# sensor.net
KiCad netlist of a schematic drawn in Altium Designer
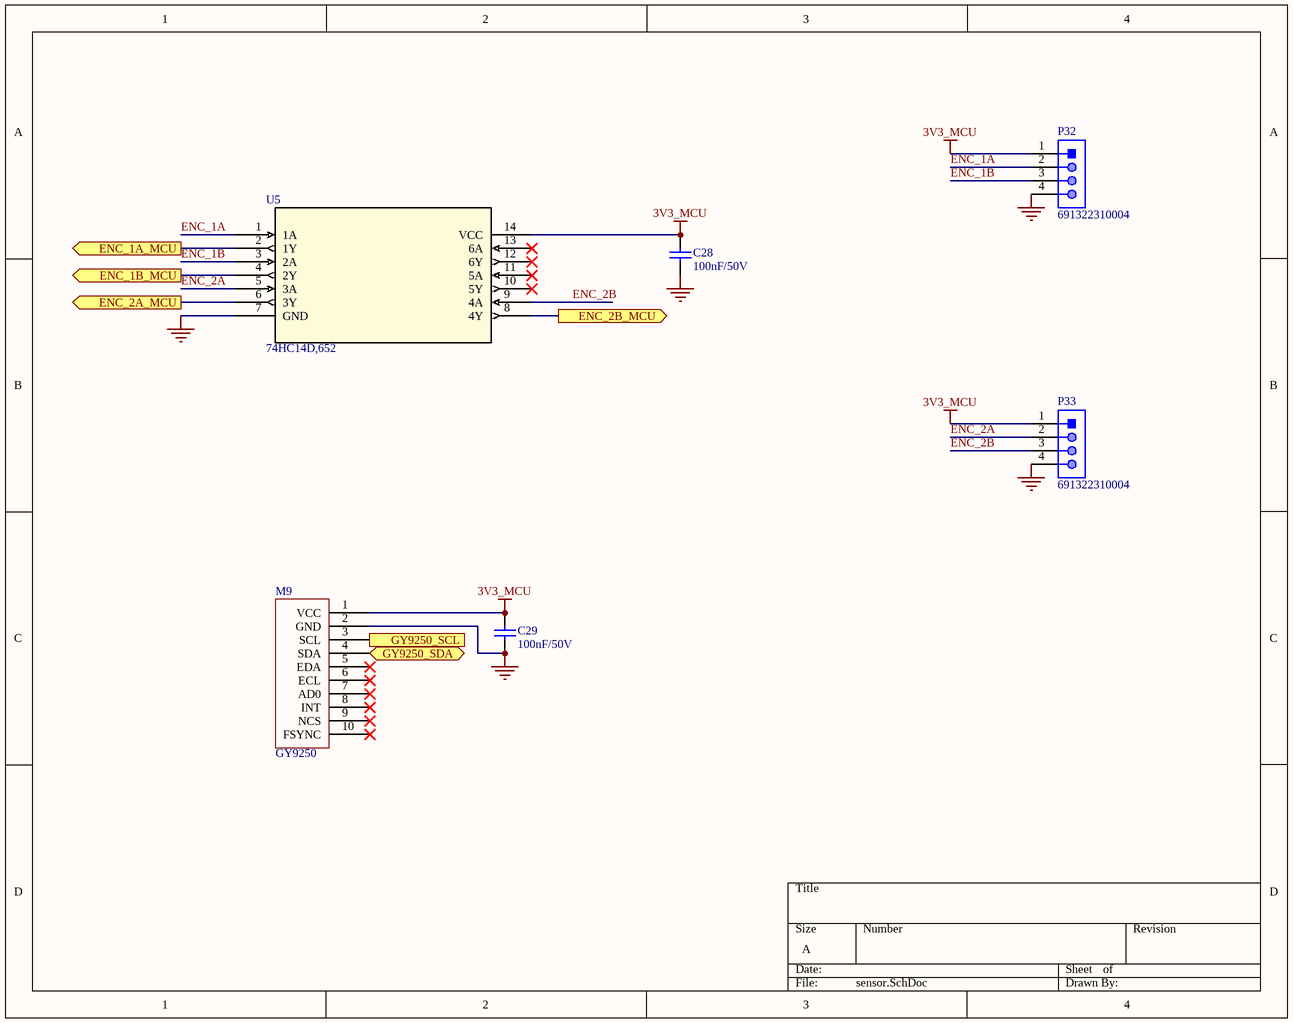
[diagram p0: sensor.SchDoc]

(export (version "E")
  (design (tool "Eeschema 10.0.6"))
  (components
    (comp (ref "C28")
      (value "100nF/50V")
      (footprint "CAP-SM-0805")
      (description "CAP CER 0.1UF 50V Y5V 0805")
      (fields
        (field (name "MANUFACTURER") "Samsung Electro-Mechanics")
        (field (name "MANUFACTURER PART NUMBER") "CL21F104ZBCNNNC")
      )
      (libsource (lib "Capacitor") (part "Cap-100nF-50V-0805"))
    )
    (comp (ref "C29")
      (value "100nF/50V")
      (footprint "CAP-SM-0805")
      (description "CAP CER 0.1UF 50V Y5V 0805")
      (fields
        (field (name "MANUFACTURER") "Samsung Electro-Mechanics")
        (field (name "MANUFACTURER PART NUMBER") "CL21F104ZBCNNNC")
      )
      (libsource (lib "Capacitor") (part "Cap-100nF-50V-0805"))
    )
    (comp (ref "M9") (value "GY9250") (footprint "GY9250") (libsource (lib "Schlib1") (part "GY9250")))
    (comp (ref "P32")
      (value "691322310004")
      (footprint "691322310004")
      (description "WR-TBL Serie 322 Horizontal PCB Header, Pluggable, pitch 3.81mm, 4p")
      (fields (field (name "PUBLISHER") "Wurth Elektronik"))
      (libsource (lib "691101710002_Altium_WR-TBL_rev19a") (part "691322310004"))
    )
    (comp (ref "P33")
      (value "691322310004")
      (footprint "691322310004")
      (description "WR-TBL Serie 322 Horizontal PCB Header, Pluggable, pitch 3.81mm, 4p")
      (fields (field (name "PUBLISHER") "Wurth Elektronik"))
      (libsource (lib "691101710002_Altium_WR-TBL_rev19a") (part "691322310004"))
    )
    (comp (ref "U5")
      (value "74HC14D,652")
      (footprint "SOT108-1_NEX")
      (description "No Description Available")
      (fields (field (name "COPYRIGHT") "Copyright (C) 2016 Accelerated Designs. All rights reserved"))
      (libsource (lib "Schlib1") (part "74HC14D,652"))
    )
  )
  (nets
    (net (code "1") (name "/ENC_1A") (class "Default")
      (node (ref "P32") (pin "2") (pinfunction "2_2") (pintype "passive"))
      (node (ref "U5") (pin "1") (pinfunction "1A_1") (pintype "input"))
    )
    (net (code "2") (name "/ENC_1A_MCU") (class "Default")
      (node (ref "U5") (pin "2") (pinfunction "1Y_2") (pintype "output"))
    )
    (net (code "3") (name "/ENC_1B") (class "Default")
      (node (ref "P32") (pin "3") (pinfunction "3_3") (pintype "passive"))
      (node (ref "U5") (pin "3") (pinfunction "2A_3") (pintype "input"))
    )
    (net (code "4") (name "/ENC_1B_MCU") (class "Default")
      (node (ref "U5") (pin "4") (pinfunction "2Y_4") (pintype "output"))
    )
    (net (code "5") (name "/ENC_2A") (class "Default")
      (node (ref "P33") (pin "2") (pinfunction "2_2") (pintype "passive"))
      (node (ref "U5") (pin "5") (pinfunction "3A_5") (pintype "input"))
    )
    (net (code "6") (name "/ENC_2A_MCU") (class "Default")
      (node (ref "U5") (pin "6") (pinfunction "3Y_6") (pintype "output"))
    )
    (net (code "7") (name "/ENC_2B") (class "Default")
      (node (ref "P33") (pin "3") (pinfunction "3_3") (pintype "passive"))
      (node (ref "U5") (pin "9") (pinfunction "4A_9") (pintype "input"))
    )
    (net (code "8") (name "/ENC_2B_MCU") (class "Default")
      (node (ref "U5") (pin "8") (pinfunction "4Y_8") (pintype "output"))
    )
    (net (code "9") (name "/GY9250_SCL") (class "Default")
      (node (ref "M9") (pin "3") (pinfunction "SCL_3") (pintype "passive"))
    )
    (net (code "10") (name "/GY9250_SDA") (class "Default")
      (node (ref "M9") (pin "4") (pinfunction "SDA_4") (pintype "passive"))
    )
    (net (code "11") (name "3V3_MCU") (class "Default")
      (node (ref "C28") (pin "2") (pinfunction "2_2") (pintype "passive"))
      (node (ref "C29") (pin "2") (pinfunction "2_2") (pintype "passive"))
      (node (ref "M9") (pin "1") (pinfunction "VCC_1") (pintype "passive"))
      (node (ref "P32") (pin "1") (pinfunction "1_1") (pintype "passive"))
      (node (ref "P33") (pin "1") (pinfunction "1_1") (pintype "passive"))
      (node (ref "U5") (pin "14") (pinfunction "VCC_14") (pintype "power_in"))
    )
    (net (code "12") (name "GND") (class "Default")
      (node (ref "C28") (pin "1") (pinfunction "1_1") (pintype "passive"))
      (node (ref "C29") (pin "1") (pinfunction "1_1") (pintype "passive"))
      (node (ref "M9") (pin "2") (pinfunction "GND_2") (pintype "passive"))
      (node (ref "P32") (pin "4") (pinfunction "4_4") (pintype "passive"))
      (node (ref "P33") (pin "4") (pinfunction "4_4") (pintype "passive"))
      (node (ref "U5") (pin "7") (pinfunction "GND_7") (pintype "power_in"))
    )
    (net (code "13") (name "unconnected-(M9-AD0-Pad7)") (class "Default")
      (node (ref "M9") (pin "7") (pinfunction "AD0_7") (pintype "passive+no_connect"))
    )
    (net (code "14") (name "unconnected-(M9-ECL-Pad6)") (class "Default")
      (node (ref "M9") (pin "6") (pinfunction "ECL_6") (pintype "passive+no_connect"))
    )
    (net (code "15") (name "unconnected-(M9-EDA-Pad5)") (class "Default")
      (node (ref "M9") (pin "5") (pinfunction "EDA_5") (pintype "passive+no_connect"))
    )
    (net (code "16") (name "unconnected-(M9-FSYNC-Pad10)") (class "Default")
      (node (ref "M9") (pin "10") (pinfunction "FSYNC_10") (pintype "passive+no_connect"))
    )
    (net (code "17") (name "unconnected-(M9-INT-Pad8)") (class "Default")
      (node (ref "M9") (pin "8") (pinfunction "INT_8") (pintype "passive+no_connect"))
    )
    (net (code "18") (name "unconnected-(M9-NCS-Pad9)") (class "Default")
      (node (ref "M9") (pin "9") (pinfunction "NCS_9") (pintype "passive+no_connect"))
    )
    (net (code "19") (name "unconnected-(U5-5A-Pad11)") (class "Default")
      (node (ref "U5") (pin "11") (pinfunction "5A_11") (pintype "input+no_connect"))
    )
    (net (code "20") (name "unconnected-(U5-5Y-Pad10)") (class "Default")
      (node (ref "U5") (pin "10") (pinfunction "5Y_10") (pintype "output+no_connect"))
    )
    (net (code "21") (name "unconnected-(U5-6A-Pad13)") (class "Default")
      (node (ref "U5") (pin "13") (pinfunction "6A_13") (pintype "input+no_connect"))
    )
    (net (code "22") (name "unconnected-(U5-6Y-Pad12)") (class "Default")
      (node (ref "U5") (pin "12") (pinfunction "6Y_12") (pintype "output+no_connect"))
    )
  )
)
